# Display_Memory.net
KiCad netlist of a schematic drawn in Altium Designer
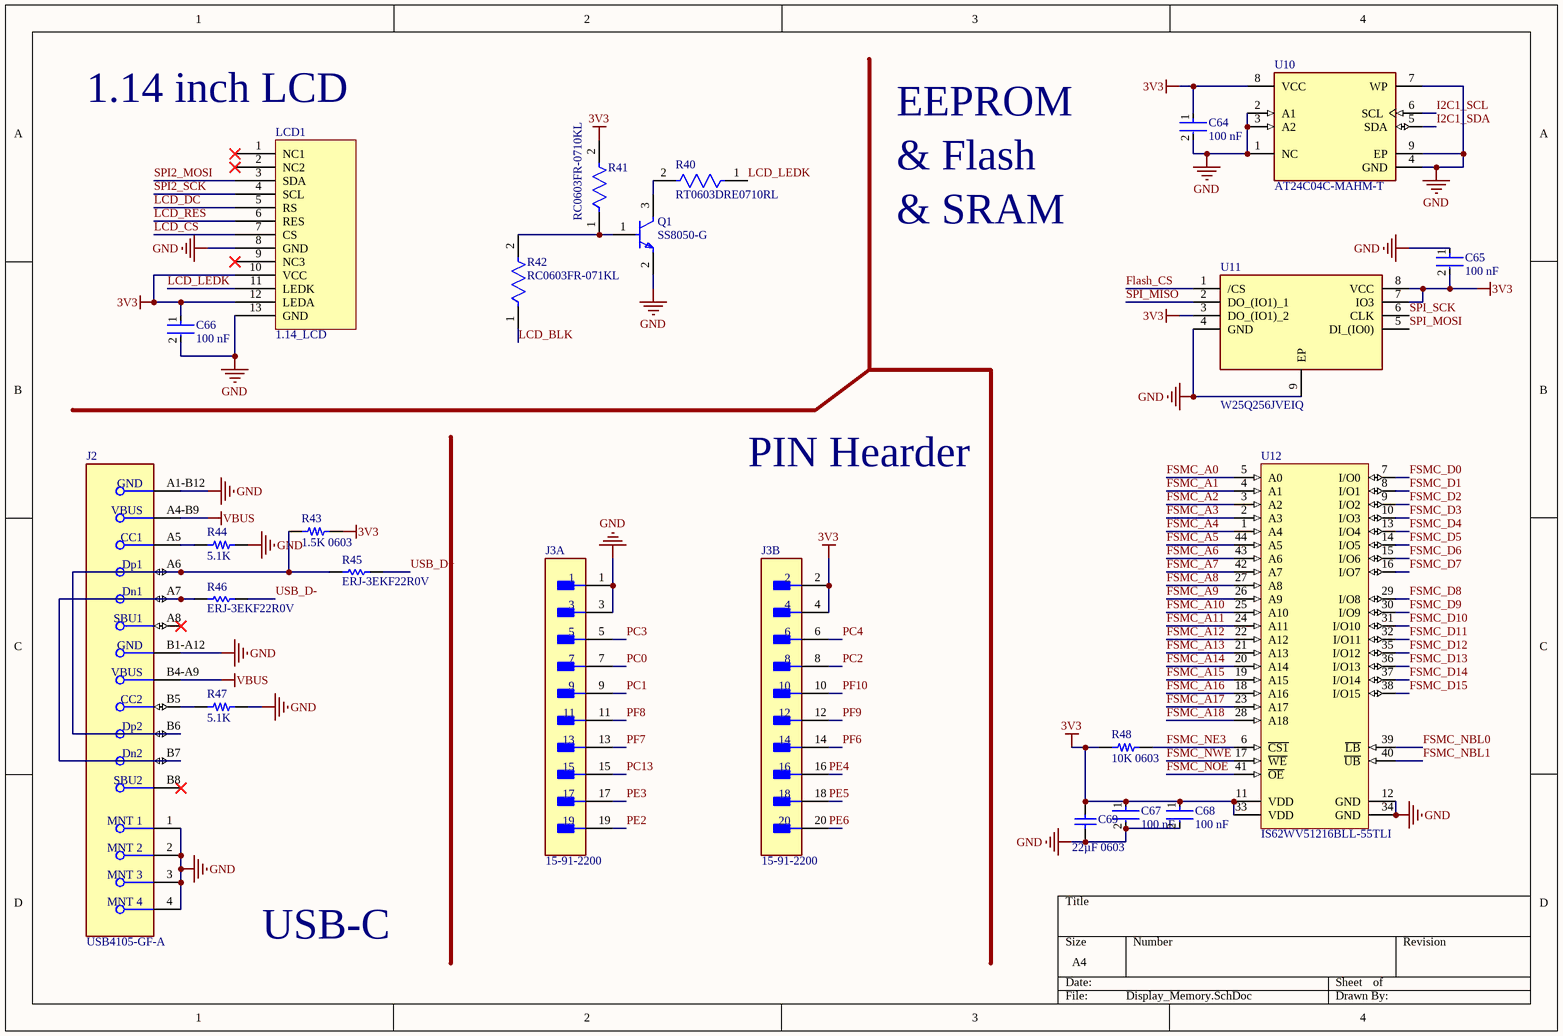
[diagram p0: Display_Memory.SchDoc]

(export (version "E")
  (design (tool "Eeschema 10.0.6"))
  (components
    (comp (ref "C64")
      (value "100 nF")
      (footprint "FP-CL10-IPC_A")
      (description "Cap Ceramic 100nF 100V X7R ±10% Pad SMD 0603 +125°C T/R")
      (fields (field (name "TOLERANCE") "10%"))
      (libsource (lib "Altium Content Vault") (part "b4654b650e69147ec39a6b967a45e02"))
    )
    (comp (ref "C65")
      (value "100 nF")
      (footprint "FP-CL10-IPC_A")
      (description "Cap Ceramic 100nF 100V X7R ±10% Pad SMD 0603 +125°C T/R")
      (fields (field (name "TOLERANCE") "10%"))
      (libsource (lib "Altium Content Vault") (part "b4654b650e69147ec39a6b967a45e02"))
    )
    (comp (ref "C66")
      (value "100 nF")
      (footprint "FP-CL10-IPC_A")
      (description "Cap Ceramic 100nF 100V X7R ±10% Pad SMD 0603 +125°C T/R")
      (fields (field (name "TOLERANCE") "10%"))
      (libsource (lib "Altium Content Vault") (part "b4654b650e69147ec39a6b967a45e02"))
    )
    (comp (ref "C67")
      (value "100 nF")
      (footprint "FP-CL10-IPC_A")
      (description "Cap Ceramic 100nF 100V X7R ±10% Pad SMD 0603 +125°C T/R")
      (fields (field (name "TOLERANCE") "10%"))
      (libsource (lib "Altium Content Vault") (part "b4654b650e69147ec39a6b967a45e02"))
    )
    (comp (ref "C68")
      (value "100 nF")
      (footprint "FP-CL10-IPC_A")
      (description "Cap Ceramic 100nF 100V X7R ±10% Pad SMD 0603 +125°C T/R")
      (fields (field (name "TOLERANCE") "10%"))
      (libsource (lib "Altium Content Vault") (part "b4654b650e69147ec39a6b967a45e02"))
    )
    (comp (ref "C69")
      (value "22µF 0603")
      (footprint "CAPC1608X100X20ML10")
      (description "Chip Capacitor, 22 uF, +/- 20%, 6.3 V, -55 to 85 degC, 1608 (0603 Metric), RoHS, Tape and Reel")
      (fields
        (field (name "TOLERANCE") "±20%")
        (field (name "PCN PART NUMBER") "MLCCPartNumberChange30/Nov/2012")
      )
      (libsource (lib "Altium Content Vault") (part "CAP-NP-2"))
    )
    (comp (ref "J2")
      (value "USB4105-GF-A")
      (footprint "FP-USB4105-GF-A-MFG")
      (description "CONN RCPT USB2.0 TYPEC 5A")
      (fields
        (field (name "MANUFACTURER") "GCT")
        (field (name "OCTOPART") "https://octopart.com/usb4105-gf-a-gct-106627878")
      )
      (libsource (lib "Altium Content Vault") (part "e7c17a616881a82b79941196b4bec10"))
    )
    (comp (ref "J3")
      (value "15-91-2200")
      (footprint "FP-15-91-2200-MFG")
      (description "15-91-2200 Conn Unshrouded Header HDR 20 POS 2.54mm Solder ST Top Entry SMD C-Grid® Tube")
      (libsource (lib "Altium Content Vault") (part "3c9050f31bf3a235369f849c918cfe7"))
    )
    (comp (ref "LCD1") (value "1.14_LCD") (footprint "1.14_LCD") (libsource (lib "Demo") (part "1.14 LCD")))
    (comp (ref "Q1")
      (value "SS8050-G")
      (footprint "FP-SS8050-G-MFG")
      (description "NPN TRANSISTOR 1.5A 40V SOT-23 R")
      (libsource (lib "Altium Content Vault") (part "2a1388f82443b098dcd57d24ac7632d"))
    )
    (comp (ref "R40")
      (value "RT0603DRE0710RL")
      (footprint "FP-RT0603-MFG")
      (description "RES SMD 10 OHM 0.5% 1/10W 0603")
      (fields (field (name "TOLERANCE") "0.005") (field (name "MANUFACTURER") "Yageo"))
      (libsource (lib "Altium Content Vault") (part "1029c3af85768c4190bb7ad29bc67b5"))
    )
    (comp (ref "R41")
      (value "RC0603FR-0710KL")
      (footprint "FP-RC0603-0_55-IPC_C")
      (description "RES 10K OHM 1% 1/10W 0603")
      (fields (field (name "TOLERANCE") "1%"))
      (libsource (lib "Altium Content Vault") (part "1029c3af85768c4190bb7ad29bc67b5"))
    )
    (comp (ref "R42")
      (value "RC0603FR-071KL")
      (footprint "FP-RC0603-0_55-IPC_C")
      (description "RES 1K OHM 1% 1/10W 0603")
      (fields (field (name "TOLERANCE") "1%"))
      (libsource (lib "Altium Content Vault") (part "1029c3af85768c4190bb7ad29bc67b5"))
    )
    (comp (ref "R43")
      (value "1.5K 0603")
      (footprint "5.1K_0603")
      (description "SMT Resistor")
      (libsource (lib "Demo") (part "5.1K_0603"))
    )
    (comp (ref "R44")
      (value "5.1K")
      (footprint "5.1K_0603")
      (description "SMT Resistor")
      (libsource (lib "Demo") (part "5.1K_0603"))
    )
    (comp (ref "R45")
      (value "ERJ-3EKF22R0V")
      (footprint "RESC1608X55X30LL15T15")
      (description "Chip Resistor, 22 Ohm, +/- 1%, 0.1 W, -55 to 155 degC, 0603 (1608 Metric), RoHS, Tape and Reel")
      (libsource (lib "Altium Content Vault") (part "RES-2"))
    )
    (comp (ref "R46")
      (value "ERJ-3EKF22R0V")
      (footprint "RESC1608X55X30LL15T15")
      (description "Chip Resistor, 22 Ohm, +/- 1%, 0.1 W, -55 to 155 degC, 0603 (1608 Metric), RoHS, Tape and Reel")
      (libsource (lib "Altium Content Vault") (part "RES-2"))
    )
    (comp (ref "R47")
      (value "5.1K")
      (footprint "5.1K_0603")
      (description "SMT Resistor")
      (libsource (lib "Demo") (part "5.1K_0603"))
    )
    (comp (ref "R48")
      (value "10K 0603")
      (footprint "5.1K_0603")
      (description "SMT Resistor")
      (libsource (lib "Demo") (part "5.1K_0603"))
    )
    (comp (ref "U10")
      (value "AT24C04C-MAHM-T")
      (footprint "FP-C04-21355-Q4B-IPC_B")
      (description "IC EEPROM 4KBIT I2C 1MHZ 8UDFN")
      (libsource (lib "Altium Content Vault") (part "94da826279c6e6069df6e860fe9c8cd"))
    )
    (comp (ref "U11")
      (value "W25Q256JVEIQ")
      (footprint "W25Q256JVEIQ")
      (description "256M-bit Serial Flash Memory with uniform 4KB sectors and Dual/Quad SPI")
      (fields (field (name "MOUSER PART NUMBER") "454-W25Q256JVEIQ"))
      (libsource (lib "Demo") (part "W25Q256JVEIQ"))
    )
    (comp (ref "U12")
      (value "IS62WV51216BLL-55TLI")
      (footprint "ISSI-TSOP-2-44_N")
      (fields (field (name "MANUFACTURER") "Integrated Silicon Solution Inc (ISSI)"))
      (libsource (lib "Altium Content Vault") (part "ISSI-IS62WV51216ALL_BLL-TSOP-2-44"))
    )
  )
  (nets
    (net (code "1") (name "/FSMC_A0") (class "Default")
      (node (ref "U12") (pin "5") (pinfunction "A0_5") (pintype "input"))
    )
    (net (code "2") (name "/FSMC_A1") (class "Default")
      (node (ref "U12") (pin "4") (pinfunction "A1_4") (pintype "input"))
    )
    (net (code "3") (name "/FSMC_A2") (class "Default")
      (node (ref "U12") (pin "3") (pinfunction "A2_3") (pintype "input"))
    )
    (net (code "4") (name "/FSMC_A3") (class "Default")
      (node (ref "U12") (pin "2") (pinfunction "A3_2") (pintype "input"))
    )
    (net (code "5") (name "/FSMC_A4") (class "Default")
      (node (ref "U12") (pin "1") (pinfunction "A4_1") (pintype "input"))
    )
    (net (code "6") (name "/FSMC_A5") (class "Default")
      (node (ref "U12") (pin "44") (pinfunction "A5_44") (pintype "input"))
    )
    (net (code "7") (name "/FSMC_A6") (class "Default")
      (node (ref "U12") (pin "43") (pinfunction "A6_43") (pintype "input"))
    )
    (net (code "8") (name "/FSMC_A7") (class "Default")
      (node (ref "U12") (pin "42") (pinfunction "A7_42") (pintype "input"))
    )
    (net (code "9") (name "/FSMC_A8") (class "Default")
      (node (ref "U12") (pin "27") (pinfunction "A8_27") (pintype "input"))
    )
    (net (code "10") (name "/FSMC_A9") (class "Default")
      (node (ref "U12") (pin "26") (pinfunction "A9_26") (pintype "input"))
    )
    (net (code "11") (name "/FSMC_A10") (class "Default")
      (node (ref "U12") (pin "25") (pinfunction "A10_25") (pintype "input"))
    )
    (net (code "12") (name "/FSMC_A11") (class "Default")
      (node (ref "U12") (pin "24") (pinfunction "A11_24") (pintype "input"))
    )
    (net (code "13") (name "/FSMC_A12") (class "Default")
      (node (ref "U12") (pin "22") (pinfunction "A12_22") (pintype "input"))
    )
    (net (code "14") (name "/FSMC_A13") (class "Default")
      (node (ref "U12") (pin "21") (pinfunction "A13_21") (pintype "input"))
    )
    (net (code "15") (name "/FSMC_A14") (class "Default")
      (node (ref "U12") (pin "20") (pinfunction "A14_20") (pintype "input"))
    )
    (net (code "16") (name "/FSMC_A15") (class "Default")
      (node (ref "U12") (pin "19") (pinfunction "A15_19") (pintype "input"))
    )
    (net (code "17") (name "/FSMC_A16") (class "Default")
      (node (ref "U12") (pin "18") (pinfunction "A16_18") (pintype "input"))
    )
    (net (code "18") (name "/FSMC_A17") (class "Default")
      (node (ref "U12") (pin "23") (pinfunction "A17_23") (pintype "input"))
    )
    (net (code "19") (name "/FSMC_A18") (class "Default")
      (node (ref "U12") (pin "28") (pinfunction "A18_28") (pintype "input"))
    )
    (net (code "20") (name "/FSMC_D0") (class "Default")
      (node (ref "U12") (pin "7") (pinfunction "I/O0_7") (pintype "bidirectional"))
    )
    (net (code "21") (name "/FSMC_D1") (class "Default")
      (node (ref "U12") (pin "8") (pinfunction "I/O1_8") (pintype "bidirectional"))
    )
    (net (code "22") (name "/FSMC_D2") (class "Default")
      (node (ref "U12") (pin "9") (pinfunction "I/O2_9") (pintype "bidirectional"))
    )
    (net (code "23") (name "/FSMC_D3") (class "Default")
      (node (ref "U12") (pin "10") (pinfunction "I/O3_10") (pintype "bidirectional"))
    )
    (net (code "24") (name "/FSMC_D4") (class "Default")
      (node (ref "U12") (pin "13") (pinfunction "I/O4_13") (pintype "bidirectional"))
    )
    (net (code "25") (name "/FSMC_D5") (class "Default")
      (node (ref "U12") (pin "14") (pinfunction "I/O5_14") (pintype "bidirectional"))
    )
    (net (code "26") (name "/FSMC_D6") (class "Default")
      (node (ref "U12") (pin "15") (pinfunction "I/O6_15") (pintype "bidirectional"))
    )
    (net (code "27") (name "/FSMC_D7") (class "Default")
      (node (ref "U12") (pin "16") (pinfunction "I/O7_16") (pintype "bidirectional"))
    )
    (net (code "28") (name "/FSMC_D8") (class "Default")
      (node (ref "U12") (pin "29") (pinfunction "I/O8_29") (pintype "bidirectional"))
    )
    (net (code "29") (name "/FSMC_D9") (class "Default")
      (node (ref "U12") (pin "30") (pinfunction "I/O9_30") (pintype "bidirectional"))
    )
    (net (code "30") (name "/FSMC_D10") (class "Default")
      (node (ref "U12") (pin "31") (pinfunction "I/O10_31") (pintype "bidirectional"))
    )
    (net (code "31") (name "/FSMC_D11") (class "Default")
      (node (ref "U12") (pin "32") (pinfunction "I/O11_32") (pintype "bidirectional"))
    )
    (net (code "32") (name "/FSMC_D12") (class "Default")
      (node (ref "U12") (pin "35") (pinfunction "I/O12_35") (pintype "bidirectional"))
    )
    (net (code "33") (name "/FSMC_D13") (class "Default")
      (node (ref "U12") (pin "36") (pinfunction "I/O13_36") (pintype "bidirectional"))
    )
    (net (code "34") (name "/FSMC_D14") (class "Default")
      (node (ref "U12") (pin "37") (pinfunction "I/O14_37") (pintype "bidirectional"))
    )
    (net (code "35") (name "/FSMC_D15") (class "Default")
      (node (ref "U12") (pin "38") (pinfunction "I/O15_38") (pintype "bidirectional"))
    )
    (net (code "36") (name "/FSMC_NBL0") (class "Default")
      (node (ref "U12") (pin "39") (pinfunction "~{LB}_39") (pintype "input"))
    )
    (net (code "37") (name "/FSMC_NBL1") (class "Default")
      (node (ref "U12") (pin "40") (pinfunction "~{UB}_40") (pintype "input"))
    )
    (net (code "38") (name "/FSMC_NE3") (class "Default")
      (node (ref "R48") (pin "2") (pinfunction "2_2") (pintype "passive"))
      (node (ref "U12") (pin "6") (pinfunction "~{CS1}_6") (pintype "input"))
    )
    (net (code "39") (name "/FSMC_NOE") (class "Default")
      (node (ref "U12") (pin "41") (pinfunction "~{OE}_41") (pintype "input"))
    )
    (net (code "40") (name "/FSMC_NWE") (class "Default")
      (node (ref "U12") (pin "17") (pinfunction "~{WE}_17") (pintype "input"))
    )
    (net (code "41") (name "/Flash_CS") (class "Default")
      (node (ref "U11") (pin "1") (pinfunction "/CS_1") (pintype "passive"))
    )
    (net (code "42") (name "/I2C1_SCL") (class "Default")
      (node (ref "U10") (pin "6") (pinfunction "SCL_6") (pintype "input"))
    )
    (net (code "43") (name "/I2C1_SDA") (class "Default")
      (node (ref "U10") (pin "5") (pinfunction "SDA_5") (pintype "bidirectional"))
    )
    (net (code "44") (name "/LCD_BLK") (class "Default")
      (node (ref "R42") (pin "1") (pinfunction "1_1") (pintype "passive"))
    )
    (net (code "45") (name "/LCD_CS") (class "Default")
      (node (ref "LCD1") (pin "7") (pinfunction "CS_7") (pintype "passive"))
    )
    (net (code "46") (name "/LCD_DC") (class "Default")
      (node (ref "LCD1") (pin "5") (pinfunction "RS_5") (pintype "passive"))
    )
    (net (code "47") (name "/LCD_LEDK") (class "Default")
      (node (ref "LCD1") (pin "11") (pinfunction "LEDK_11") (pintype "passive"))
      (node (ref "R40") (pin "1") (pinfunction "1_1") (pintype "passive"))
    )
    (net (code "48") (name "/LCD_RES") (class "Default")
      (node (ref "LCD1") (pin "6") (pinfunction "RES_6") (pintype "passive"))
    )
    (net (code "49") (name "/PC0") (class "Default")
      (node (ref "J3") (pin "7") (pinfunction "7_7") (pintype "passive"))
    )
    (net (code "50") (name "/PC1") (class "Default")
      (node (ref "J3") (pin "9") (pinfunction "9_9") (pintype "passive"))
    )
    (net (code "51") (name "/PC2") (class "Default")
      (node (ref "J3") (pin "8") (pinfunction "8_8") (pintype "passive"))
    )
    (net (code "52") (name "/PC3") (class "Default")
      (node (ref "J3") (pin "5") (pinfunction "5_5") (pintype "passive"))
    )
    (net (code "53") (name "/PC4") (class "Default")
      (node (ref "J3") (pin "6") (pinfunction "6_6") (pintype "passive"))
    )
    (net (code "54") (name "/PC13") (class "Default")
      (node (ref "J3") (pin "15") (pinfunction "15_15") (pintype "passive"))
    )
    (net (code "55") (name "/PE2") (class "Default")
      (node (ref "J3") (pin "19") (pinfunction "19_19") (pintype "passive"))
    )
    (net (code "56") (name "/PE3") (class "Default")
      (node (ref "J3") (pin "17") (pinfunction "17_17") (pintype "passive"))
    )
    (net (code "57") (name "/PE4") (class "Default")
      (node (ref "J3") (pin "16") (pinfunction "16_16") (pintype "passive"))
    )
    (net (code "58") (name "/PE5") (class "Default")
      (node (ref "J3") (pin "18") (pinfunction "18_18") (pintype "passive"))
    )
    (net (code "59") (name "/PE6") (class "Default")
      (node (ref "J3") (pin "20") (pinfunction "20_20") (pintype "passive"))
    )
    (net (code "60") (name "/PF6") (class "Default")
      (node (ref "J3") (pin "14") (pinfunction "14_14") (pintype "passive"))
    )
    (net (code "61") (name "/PF7") (class "Default")
      (node (ref "J3") (pin "13") (pinfunction "13_13") (pintype "passive"))
    )
    (net (code "62") (name "/PF8") (class "Default")
      (node (ref "J3") (pin "11") (pinfunction "11_11") (pintype "passive"))
    )
    (net (code "63") (name "/PF9") (class "Default")
      (node (ref "J3") (pin "12") (pinfunction "12_12") (pintype "passive"))
    )
    (net (code "64") (name "/PF10") (class "Default")
      (node (ref "J3") (pin "10") (pinfunction "10_10") (pintype "passive"))
    )
    (net (code "65") (name "/SPI2_MOSI") (class "Default")
      (node (ref "LCD1") (pin "3") (pinfunction "SDA_3") (pintype "passive"))
    )
    (net (code "66") (name "/SPI2_SCK") (class "Default")
      (node (ref "LCD1") (pin "4") (pinfunction "SCL_4") (pintype "passive"))
    )
    (net (code "67") (name "/SPI_MISO") (class "Default")
      (node (ref "U11") (pin "2") (pinfunction "DO_(IO1)_1_2") (pintype "passive"))
    )
    (net (code "68") (name "/SPI_MOSI") (class "Default")
      (node (ref "U11") (pin "5") (pinfunction "DI_(IO0)_5") (pintype "passive"))
    )
    (net (code "69") (name "/SPI_SCK") (class "Default")
      (node (ref "U11") (pin "6") (pinfunction "CLK_6") (pintype "passive"))
    )
    (net (code "70") (name "/USB_D+") (class "Default")
      (node (ref "R45") (pin "2") (pinfunction "2_2") (pintype "passive"))
    )
    (net (code "71") (name "/USB_D-") (class "Default")
      (node (ref "R46") (pin "2") (pinfunction "2_2") (pintype "passive"))
    )
    (net (code "72") (name "3V3") (class "Default")
      (node (ref "C64") (pin "1") (pinfunction "1_1") (pintype "passive"))
      (node (ref "C65") (pin "2") (pinfunction "2_2") (pintype "passive"))
      (node (ref "C66") (pin "1") (pinfunction "1_1") (pintype "passive"))
      (node (ref "C67") (pin "1") (pinfunction "1_1") (pintype "passive"))
      (node (ref "C68") (pin "1") (pinfunction "1_1") (pintype "passive"))
      (node (ref "C69") (pin "2") (pinfunction "2_2") (pintype "passive"))
      (node (ref "J3") (pin "2") (pinfunction "2_2") (pintype "passive"))
      (node (ref "J3") (pin "4") (pinfunction "4_4") (pintype "passive"))
      (node (ref "LCD1") (pin "10") (pinfunction "VCC_10") (pintype "passive"))
      (node (ref "LCD1") (pin "12") (pinfunction "LEDA_12") (pintype "passive"))
      (node (ref "R41") (pin "2") (pinfunction "2_2") (pintype "passive"))
      (node (ref "R43") (pin "2") (pinfunction "2_2") (pintype "passive"))
      (node (ref "R48") (pin "1") (pinfunction "1_1") (pintype "passive"))
      (node (ref "U10") (pin "8") (pinfunction "VCC_8") (pintype "power_in"))
      (node (ref "U11") (pin "3") (pinfunction "DO_(IO1)_2_3") (pintype "passive"))
      (node (ref "U11") (pin "7") (pinfunction "IO3_7") (pintype "passive"))
      (node (ref "U11") (pin "8") (pinfunction "VCC_8") (pintype "passive"))
      (node (ref "U12") (pin "11") (pinfunction "VDD_11") (pintype "power_in"))
      (node (ref "U12") (pin "33") (pinfunction "VDD_33") (pintype "power_in"))
    )
    (net (code "73") (name "GND") (class "Default")
      (node (ref "C64") (pin "2") (pinfunction "2_2") (pintype "passive"))
      (node (ref "C65") (pin "1") (pinfunction "1_1") (pintype "passive"))
      (node (ref "C66") (pin "2") (pinfunction "2_2") (pintype "passive"))
      (node (ref "C67") (pin "2") (pinfunction "2_2") (pintype "passive"))
      (node (ref "C68") (pin "2") (pinfunction "2_2") (pintype "passive"))
      (node (ref "C69") (pin "1") (pinfunction "1_1") (pintype "passive"))
      (node (ref "J2") (pin "1") (pinfunction "MNT_1_1") (pintype "passive"))
      (node (ref "J2") (pin "2") (pinfunction "MNT_2_2") (pintype "passive"))
      (node (ref "J2") (pin "3") (pinfunction "MNT_3_3") (pintype "passive"))
      (node (ref "J2") (pin "4") (pinfunction "MNT_4_4") (pintype "passive"))
      (node (ref "J2") (pin "A1-B12") (pinfunction "GND_A1-B12") (pintype "power_in"))
      (node (ref "J2") (pin "B1-A12") (pinfunction "GND_B1-A12") (pintype "power_in"))
      (node (ref "J3") (pin "1") (pinfunction "1_1") (pintype "passive"))
      (node (ref "J3") (pin "3") (pinfunction "3_3") (pintype "passive"))
      (node (ref "LCD1") (pin "13") (pinfunction "GND_13") (pintype "passive"))
      (node (ref "LCD1") (pin "8") (pinfunction "GND_8") (pintype "passive"))
      (node (ref "Q1") (pin "2") (pinfunction "E_2") (pintype "passive"))
      (node (ref "R44") (pin "2") (pinfunction "2_2") (pintype "passive"))
      (node (ref "R47") (pin "2") (pinfunction "2_2") (pintype "passive"))
      (node (ref "U10") (pin "1") (pinfunction "NC_1") (pintype "passive"))
      (node (ref "U10") (pin "2") (pinfunction "A1_2") (pintype "input"))
      (node (ref "U10") (pin "3") (pinfunction "A2_3") (pintype "input"))
      (node (ref "U10") (pin "4") (pinfunction "GND_4") (pintype "power_in"))
      (node (ref "U10") (pin "7") (pinfunction "WP_7") (pintype "passive"))
      (node (ref "U10") (pin "9") (pinfunction "EP_9") (pintype "power_in"))
      (node (ref "U11") (pin "4") (pinfunction "GND_4") (pintype "passive"))
      (node (ref "U11") (pin "9") (pinfunction "EP_9") (pintype "passive"))
      (node (ref "U12") (pin "12") (pinfunction "GND_12") (pintype "power_in"))
      (node (ref "U12") (pin "34") (pinfunction "GND_34") (pintype "power_in"))
    )
    (net (code "74") (name "Net-(J2-CC1)") (class "Default")
      (node (ref "J2") (pin "A5") (pinfunction "CC1_A5") (pintype "power_in"))
      (node (ref "R44") (pin "1") (pinfunction "1_1") (pintype "passive"))
    )
    (net (code "75") (name "Net-(J2-CC2)") (class "Default")
      (node (ref "J2") (pin "B5") (pinfunction "CC2_B5") (pintype "bidirectional"))
      (node (ref "R47") (pin "1") (pinfunction "1_1") (pintype "passive"))
    )
    (net (code "76") (name "Net-(J2-Dn1)") (class "Default")
      (node (ref "J2") (pin "A7") (pinfunction "Dn1_A7") (pintype "bidirectional"))
      (node (ref "J2") (pin "B7") (pinfunction "Dn2_B7") (pintype "bidirectional"))
      (node (ref "R46") (pin "1") (pinfunction "1_1") (pintype "passive"))
    )
    (net (code "77") (name "Net-(J2-Dp1)") (class "Default")
      (node (ref "J2") (pin "A6") (pinfunction "Dp1_A6") (pintype "bidirectional"))
      (node (ref "J2") (pin "B6") (pinfunction "Dp2_B6") (pintype "bidirectional"))
      (node (ref "R43") (pin "1") (pinfunction "1_1") (pintype "passive"))
      (node (ref "R45") (pin "1") (pinfunction "1_1") (pintype "passive"))
    )
    (net (code "78") (name "Net-(Q1-B)") (class "Default")
      (node (ref "Q1") (pin "1") (pinfunction "B_1") (pintype "passive"))
      (node (ref "R41") (pin "1") (pinfunction "1_1") (pintype "passive"))
      (node (ref "R42") (pin "2") (pinfunction "2_2") (pintype "passive"))
    )
    (net (code "79") (name "Net-(Q1-C)") (class "Default")
      (node (ref "Q1") (pin "3") (pinfunction "C_3") (pintype "passive"))
      (node (ref "R40") (pin "2") (pinfunction "2_2") (pintype "passive"))
    )
    (net (code "80") (name "VBUS") (class "Default")
      (node (ref "J2") (pin "A4-B9") (pinfunction "VBUS_A4-B9") (pintype "power_in"))
      (node (ref "J2") (pin "B4-A9") (pinfunction "VBUS_B4-A9") (pintype "power_in"))
    )
    (net (code "81") (name "unconnected-(J2-SBU1-PadA8)") (class "Default")
      (node (ref "J2") (pin "A8") (pinfunction "SBU1_A8") (pintype "bidirectional+no_connect"))
    )
    (net (code "82") (name "unconnected-(J2-SBU2-PadB8)") (class "Default")
      (node (ref "J2") (pin "B8") (pinfunction "SBU2_B8") (pintype "power_in+no_connect"))
    )
    (net (code "83") (name "unconnected-(LCD1-NC1-Pad1)") (class "Default")
      (node (ref "LCD1") (pin "1") (pinfunction "NC1_1") (pintype "passive+no_connect"))
    )
    (net (code "84") (name "unconnected-(LCD1-NC2-Pad2)") (class "Default")
      (node (ref "LCD1") (pin "2") (pinfunction "NC2_2") (pintype "passive+no_connect"))
    )
    (net (code "85") (name "unconnected-(LCD1-NC3-Pad9)") (class "Default")
      (node (ref "LCD1") (pin "9") (pinfunction "NC3_9") (pintype "passive+no_connect"))
    )
  )
)
